# power_led_button.net
KiCad netlist of a schematic drawn in EAGLE
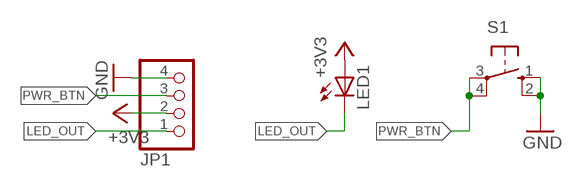
[diagram p0: schematic, sheet 1]

(export (version "E")
  (design (tool "Eeschema 10.0.6"))
  (components
    (comp (ref "JP1")
      (value "PINHD-1X4/90")
      (footprint "eagle-import:1X04_90")
      (libsource (lib "eagle-import") (part "PINHD-1X4/90"))
    )
    (comp (ref "LED1")
      (value "LED3MM")
      (footprint "eagle-import:LED3MM")
      (libsource (lib "eagle-import") (part "LED3MM"))
    )
    (comp (ref "S1")
      (value "40-XX")
      (footprint "eagle-import:B3F-40XX")
      (fields (field (name "MF") "OMRON COMPONENTS USA") (field (name "MPN") "B3F-4000"))
      (libsource (lib "eagle-import") (part "40-XX"))
    )
  )
  (nets
    (net (code "1") (name "+3V3") (class "Default")
      (node (ref "JP1") (pin "2") (pinfunction "2_2") (pintype "passive"))
      (node (ref "LED1") (pin "A") (pinfunction "A_A") (pintype "passive"))
    )
    (net (code "2") (name "GND") (class "Default")
      (node (ref "JP1") (pin "4") (pinfunction "4_4") (pintype "passive"))
      (node (ref "S1") (pin "1") (pinfunction "S_1") (pintype "passive"))
      (node (ref "S1") (pin "2") (pinfunction "S1_2") (pintype "passive"))
    )
    (net (code "3") (name "LED_OUT") (class "Default")
      (node (ref "JP1") (pin "1") (pinfunction "1_1") (pintype "passive"))
      (node (ref "LED1") (pin "K") (pinfunction "C_K") (pintype "passive"))
    )
    (net (code "4") (name "PWR_BTN") (class "Default")
      (node (ref "JP1") (pin "3") (pinfunction "3_3") (pintype "passive"))
      (node (ref "S1") (pin "3") (pinfunction "P_3") (pintype "passive"))
      (node (ref "S1") (pin "4") (pinfunction "P1_4") (pintype "passive"))
    )
  )
)
